# Powerboard.net
KiCad netlist of a schematic drawn in EAGLE
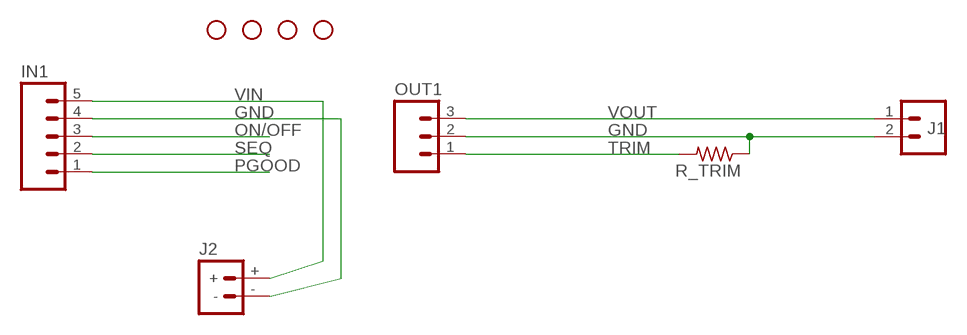
[diagram p0: schematic, sheet 1]

(export (version "E")
  (design (tool "Eeschema 10.0.6"))
  (components
    (comp (ref "IN1")
      (value "M05PTH")
      (footprint "eagle-import:1X05")
      (libsource (lib "eagle-import") (part "M05PTH"))
    )
    (comp (ref "J1")
      (value "CONN_023.5MM")
      (footprint "eagle-import:SCREWTERMINAL-3.5MM-2")
      (libsource (lib "eagle-import") (part "CONN_023.5MM"))
    )
    (comp (ref "J2")
      (value "BATTERY_CONN_DEANS")
      (footprint "eagle-import:DEANS")
      (libsource (lib "eagle-import") (part "BATTERY_CONN_DEANS"))
    )
    (comp (ref "OUT1")
      (value "M03PTH")
      (footprint "eagle-import:1X03")
      (libsource (lib "eagle-import") (part "M03PTH"))
    )
    (comp (ref "R_TRIM")
      (value "R-US_R0603")
      (footprint "eagle-import:R0603")
      (libsource (lib "eagle-import") (part "R-US_R0603"))
    )
    (comp (ref "U$2")
      (value "STAND-OFF")
      (footprint "eagle-import:STAND-OFF")
      (libsource (lib "eagle-import") (part "STAND-OFF"))
    )
    (comp (ref "U$6")
      (value "STAND-OFF")
      (footprint "eagle-import:STAND-OFF")
      (libsource (lib "eagle-import") (part "STAND-OFF"))
    )
    (comp (ref "U$7")
      (value "STAND-OFF")
      (footprint "eagle-import:STAND-OFF")
      (libsource (lib "eagle-import") (part "STAND-OFF"))
    )
    (comp (ref "U$8")
      (value "STAND-OFF")
      (footprint "eagle-import:STAND-OFF")
      (libsource (lib "eagle-import") (part "STAND-OFF"))
    )
  )
  (nets
    (net (code "1") (name "/GND") (class "Default")
      (node (ref "IN1") (pin "4") (pinfunction "4_4") (pintype "passive"))
      (node (ref "J1") (pin "2") (pinfunction "2_2") (pintype "passive"))
      (node (ref "J2") (pin "-") (pinfunction "-_-") (pintype "passive"))
      (node (ref "OUT1") (pin "2") (pinfunction "2_2") (pintype "passive"))
      (node (ref "R_TRIM") (pin "1") (pinfunction "1_1") (pintype "passive"))
    )
    (net (code "2") (name "/ON{slash}OFF") (class "Default")
      (node (ref "IN1") (pin "3") (pinfunction "3_3") (pintype "passive"))
    )
    (net (code "3") (name "/PGOOD") (class "Default")
      (node (ref "IN1") (pin "1") (pinfunction "1_1") (pintype "passive"))
    )
    (net (code "4") (name "/SEQ") (class "Default")
      (node (ref "IN1") (pin "2") (pinfunction "2_2") (pintype "passive"))
    )
    (net (code "5") (name "/TRIM") (class "Default")
      (node (ref "OUT1") (pin "1") (pinfunction "1_1") (pintype "passive"))
      (node (ref "R_TRIM") (pin "2") (pinfunction "2_2") (pintype "passive"))
    )
    (net (code "6") (name "/VIN") (class "Default")
      (node (ref "IN1") (pin "5") (pinfunction "5_5") (pintype "passive"))
      (node (ref "J2") (pin "+") (pinfunction "+_+") (pintype "passive"))
    )
    (net (code "7") (name "/VOUT") (class "Default")
      (node (ref "J1") (pin "1") (pinfunction "1_1") (pintype "passive"))
      (node (ref "OUT1") (pin "3") (pinfunction "3_3") (pintype "passive"))
    )
  )
)
